# Main.net
KiCad netlist of a schematic drawn in Altium Designer
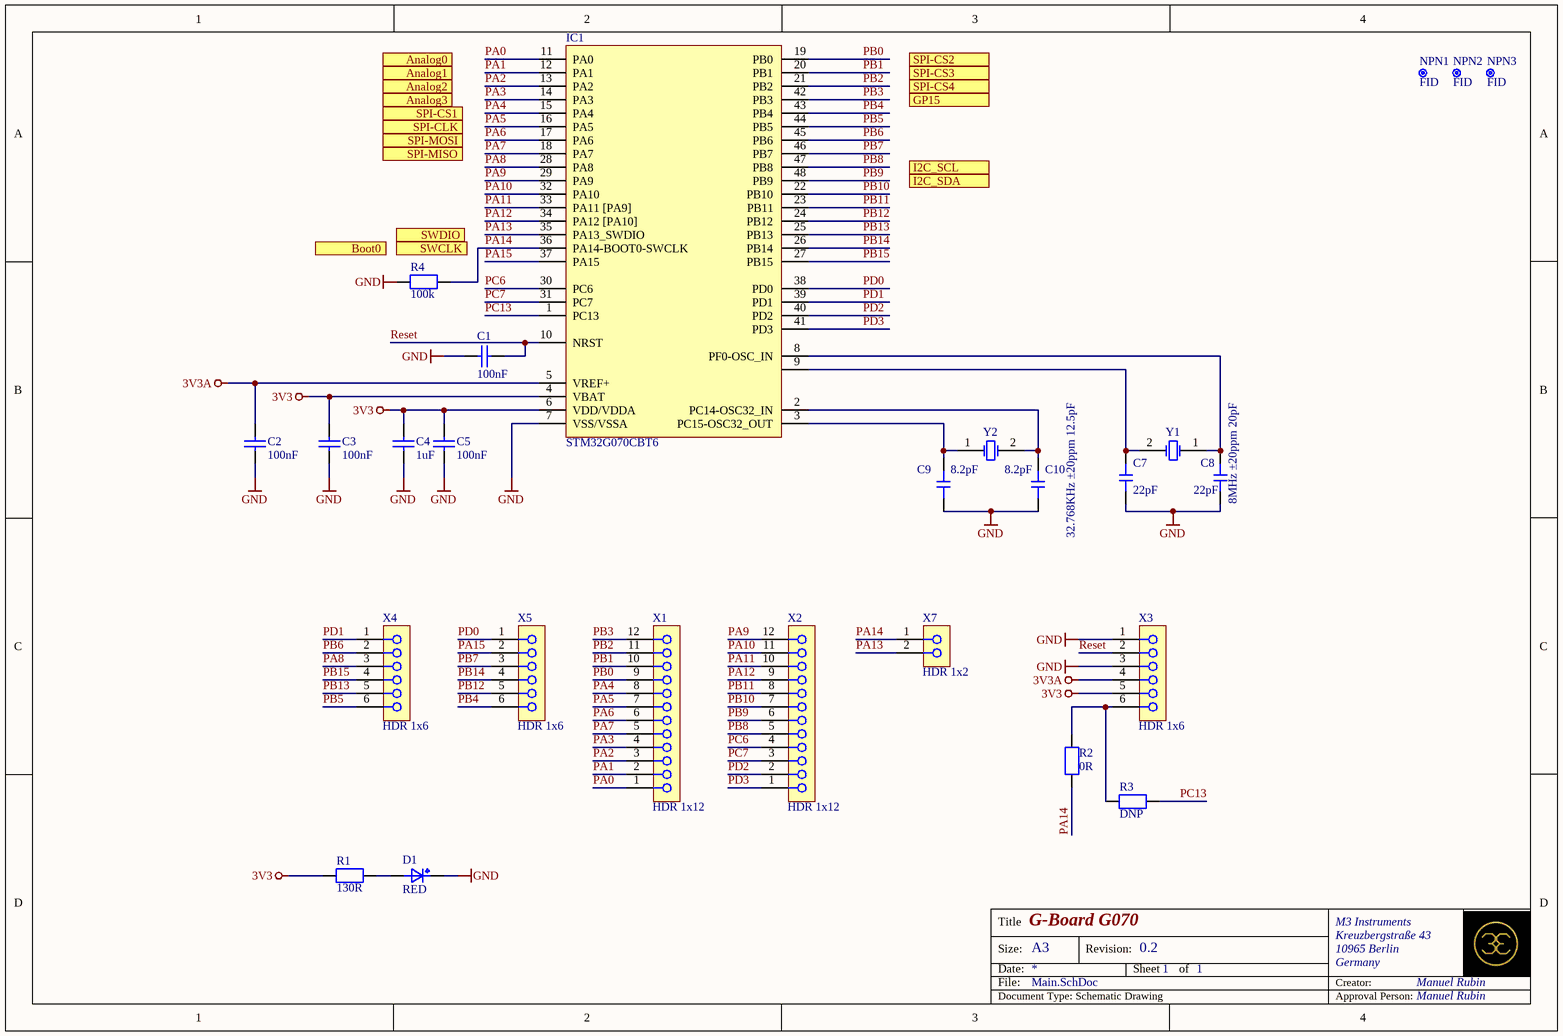
[diagram p0: Main.SchDoc]

(export (version "E")
  (design (tool "Eeschema 10.0.6"))
  (components
    (comp (ref "C1")
      (value "100nF")
      (footprint "CAPC1005X55")
      (description "X7R 100nF ±10% 16V 0402 Multilayer Ceramic Capacitors MLCC - SMD/SMT ROHS")
      (fields
        (field (name "MANUFACTURER") "Samsung Electro-Mechanics")
        (field (name "MANUFACTURER PART NUMBER") "CL05B104KO5NNNC")
      )
      (libsource (lib "Caps") (part "CAP_100nF_0402"))
    )
    (comp (ref "C2")
      (value "100nF")
      (footprint "CAPC1005X55")
      (description "X7R 100nF ±10% 16V 0402 Multilayer Ceramic Capacitors MLCC - SMD/SMT ROHS")
      (fields
        (field (name "MANUFACTURER") "Samsung Electro-Mechanics")
        (field (name "MANUFACTURER PART NUMBER") "CL05B104KO5NNNC")
      )
      (libsource (lib "Caps") (part "CAP_100nF_0402"))
    )
    (comp (ref "C3")
      (value "100nF")
      (footprint "CAPC1005X55")
      (description "X7R 100nF ±10% 16V 0402 Multilayer Ceramic Capacitors MLCC - SMD/SMT ROHS")
      (fields
        (field (name "MANUFACTURER") "Samsung Electro-Mechanics")
        (field (name "MANUFACTURER PART NUMBER") "CL05B104KO5NNNC")
      )
      (libsource (lib "Caps") (part "CAP_100nF_0402"))
    )
    (comp (ref "C4")
      (value "1uF")
      (footprint "CAPC1005X55")
      (description "X5R 25V ±10% 1uF 0402 Multilayer Ceramic Capacitors MLCC - SMD/SMT ROHS")
      (fields
        (field (name "MANUFACTURER") "Samsung Electro-Mechanics")
        (field (name "MANUFACTURER PART NUMBER") "CL05A105KA5NQNC")
      )
      (libsource (lib "Caps") (part "CAP_1uF_0402"))
    )
    (comp (ref "C5")
      (value "100nF")
      (footprint "CAPC1005X55")
      (description "X7R 100nF ±10% 16V 0402 Multilayer Ceramic Capacitors MLCC - SMD/SMT ROHS")
      (fields
        (field (name "MANUFACTURER") "Samsung Electro-Mechanics")
        (field (name "MANUFACTURER PART NUMBER") "CL05B104KO5NNNC")
      )
      (libsource (lib "Caps") (part "CAP_100nF_0402"))
    )
    (comp (ref "C7")
      (value "22pF")
      (footprint "CAPC1608X95N")
      (description "Chip capacitors")
      (fields
        (field (name "MANUFACTURER") "Samsung Electro-Mechanics")
        (field (name "MANUFACTURER PART NUMBER") "CL10C220JB8NNNC")
      )
      (libsource (lib "Caps") (part "CAP_22pF_50V_0603"))
    )
    (comp (ref "C8")
      (value "22pF")
      (footprint "CAPC1608X95N")
      (description "Chip capacitors")
      (fields
        (field (name "MANUFACTURER") "Samsung Electro-Mechanics")
        (field (name "MANUFACTURER PART NUMBER") "CL10C220JB8NNNC")
      )
      (libsource (lib "Caps") (part "CAP_22pF_50V_0603"))
    )
    (comp (ref "C9")
      (value "8.2pF")
      (footprint "CAPC1608X95N")
      (description "Multilayer Ceramic Capacitors MLCC - SMD/SMT 0402 8.0pF 50volts C0G +/-0.5pF")
      (fields
        (field (name "MANUFACTURER") "Guangdong Fenghua Advanced Tech")
        (field (name "MANUFACTURER PART NUMBER") "0603CG8R2C500NT")
      )
      (libsource (lib "Caps") (part "CAP_8p2_50V_0603"))
    )
    (comp (ref "C10")
      (value "8.2pF")
      (footprint "CAPC1608X95N")
      (description "Multilayer Ceramic Capacitors MLCC - SMD/SMT 0402 8.0pF 50volts C0G +/-0.5pF")
      (fields
        (field (name "MANUFACTURER") "Guangdong Fenghua Advanced Tech")
        (field (name "MANUFACTURER PART NUMBER") "0603CG8R2C500NT")
      )
      (libsource (lib "Caps") (part "CAP_8p2_50V_0603"))
    )
    (comp (ref "D1")
      (value "RED")
      (footprint "WL-SMCW_0805")
      (description "Standard LEDs - SMD WL-SMCW SMDMono TpVw Waterclr 0805 Red")
      (fields
        (field (name "MANUFACTURER") "Wurth Elektronik")
        (field (name "MANUFACTURER PART NUMBER") "150080RS75000")
      )
      (libsource (lib "Diodes") (part "LED_0805_RED_AK"))
    )
    (comp (ref "IC1")
      (value "STM32G070CBT6")
      (footprint "LQFP-48_7x7x05P")
      (fields (field (name "MANUFACTURER") "STMicroelectronics"))
      (libsource (lib "ICs") (part "STM32G070CBT6"))
    )
    (comp (ref "NPN1")
      (value "FID")
      (footprint "Fiducial_1mm")
      (libsource (lib "MISC") (part "Fiducial_1mm"))
    )
    (comp (ref "NPN2")
      (value "FID")
      (footprint "Fiducial_1mm")
      (libsource (lib "MISC") (part "Fiducial_1mm"))
    )
    (comp (ref "NPN3")
      (value "FID")
      (footprint "Fiducial_1mm")
      (libsource (lib "MISC") (part "Fiducial_1mm"))
    )
    (comp (ref "R1")
      (value "130R")
      (footprint "RESC2012X70N")
      (description "Dickfilmwiderstände - SMD 1/8watt 130ohms 1% 100ppm")
      (fields
        (field (name "MANUFACTURER") "Vishay / Dale")
        (field (name "MANUFACTURER PART NUMBER") "CRCW0805130RFKEA")
      )
      (libsource (lib "Resistors") (part "RES_130R_0805"))
    )
    (comp (ref "R2")
      (value "0R")
      (footprint "RESC1608X55N")
      (description "Thick Film Resistors - SMD 1/10watt ZEROohm Jumper")
      (fields
        (field (name "MANUFACTURER") "Vishay")
        (field (name "MANUFACTURER PART NUMBER") "CRCW06030000Z0EA")
      )
      (libsource (lib "Resistors") (part "RES_0R_0603"))
    )
    (comp (ref "R3")
      (value "DNP")
      (footprint "RESC1608X55N")
      (description "Resistor SMD 0603 - not populated")
      (libsource (lib "Resistors") (part "RES_DNF_0603"))
    )
    (comp (ref "R4")
      (value "100k")
      (footprint "RESC1005X40N")
      (description "Thick Film Resistors - SMD 63mW 100Kohms 1%")
      (fields
        (field (name "MANUFACTURER") "Vishay")
        (field (name "MANUFACTURER PART NUMBER") "RC0402FR-07100KL")
      )
      (libsource (lib "Gfs_Library") (part "RES_100k_0402"))
    )
    (comp (ref "X1")
      (value "HDR 1x12")
      (footprint "61301211121_no")
      (description "Board-to-Board-Steckverbinder, 2.54 mm, 12 Kontakt(e), Stiftleiste 1-Reihig")
      (fields (field (name "MANUFACTURER") "WE") (field (name "MANUFACTURER PART NUMBER") "61301211121"))
      (libsource (lib "Connectors") (part "CON_HEADER_1X12_no_overlay"))
    )
    (comp (ref "X2")
      (value "HDR 1x12")
      (footprint "61301211121_no")
      (description "Board-to-Board-Steckverbinder, 2.54 mm, 12 Kontakt(e), Stiftleiste 1-Reihig")
      (fields (field (name "MANUFACTURER") "WE") (field (name "MANUFACTURER PART NUMBER") "61301211121"))
      (libsource (lib "Connectors") (part "CON_HEADER_1X12_no_overlay"))
    )
    (comp (ref "X3")
      (value "HDR 1x6")
      (footprint "61300611121_no")
      (description "Board-to-Board-Steckverbinder, 2.54 mm, 6 Kontakt(e), Stiftleiste 1-Reihig")
      (fields (field (name "MANUFACTURER") "WE") (field (name "MANUFACTURER PART NUMBER") "61300611121"))
      (libsource (lib "Connectors") (part "CON_HEADER_1X6_no_overlay"))
    )
    (comp (ref "X4")
      (value "HDR 1x6")
      (footprint "61300611121_no")
      (description "Board-to-Board-Steckverbinder, 2.54 mm, 6 Kontakt(e), Stiftleiste 1-Reihig")
      (fields (field (name "MANUFACTURER") "WE") (field (name "MANUFACTURER PART NUMBER") "61300611121"))
      (libsource (lib "Connectors") (part "CON_HEADER_1X6_no_overlay"))
    )
    (comp (ref "X5")
      (value "HDR 1x6")
      (footprint "61300611121_no")
      (description "Board-to-Board-Steckverbinder, 2.54 mm, 6 Kontakt(e), Stiftleiste 1-Reihig")
      (fields (field (name "MANUFACTURER") "WE") (field (name "MANUFACTURER PART NUMBER") "61300611121"))
      (libsource (lib "Connectors") (part "CON_HEADER_1X6_no_overlay"))
    )
    (comp (ref "X7")
      (value "HDR 1x2")
      (footprint "CON_HEADER2.54_1x2W_no")
      (description "Board-to-Board-Steckverbinder, 2.54 mm, 2 Kontakt(e), Stiftleiste 1-Reihig")
      (fields
        (field (name "MANUFACTURER") "Samtec")
        (field (name "MANUFACTURER PART NUMBER") "TSW-102-07-T-S")
      )
      (libsource (lib "Connectors") (part "CON_HEADER_1X2_no_overlay"))
    )
    (comp (ref "Y1")
      (value "8MHz ±20ppm 20pF")
      (footprint "SMD-5032_2P")
      (description "8MHz SMD Crystal Resonator 20pF ±10ppm ±50ppm -40℃~+85℃ SMD5032-2P Crystals ROHS")
      (fields
        (field (name "MANUFACTURER") "Yangxing Tech")
        (field (name "MANUFACTURER PART NUMBER") "X50328MSB2GI")
      )
      (libsource (lib "MISC") (part "SMD-5032_2P 8MHz 20ppm 20pF"))
    )
    (comp (ref "Y2")
      (value "32.768KHz ±20ppm 12.5pF")
      (footprint "SMD-3215_2P FC - 135")
      (description "32.768kHz SMD Crystal Resonator 12.5pF 70kΩ ±20ppm -40℃~+85℃ SMD3215-2P Crystals ROHS")
      (fields
        (field (name "MANUFACTURER") "Seiko Epson")
        (field (name "MANUFACTURER PART NUMBER") "Q13FC1350000400")
      )
      (libsource (lib "MISC") (part "SMD-3215_2P 32.768KHz 20ppm 12.5pF"))
    )
  )
  (nets
    (net (code "9") (name "/PA0") (class "Default")
      (node (ref "IC1") (pin "11") (pinfunction "PA0_11") (pintype "passive"))
      (node (ref "X1") (pin "1") (pinfunction "1_1") (pintype "passive"))
    )
    (net (code "10") (name "/PA1") (class "Default")
      (node (ref "IC1") (pin "12") (pinfunction "PA1_12") (pintype "passive"))
      (node (ref "X1") (pin "2") (pinfunction "2_2") (pintype "passive"))
    )
    (net (code "11") (name "/PA2") (class "Default")
      (node (ref "IC1") (pin "13") (pinfunction "PA2_13") (pintype "passive"))
      (node (ref "X1") (pin "3") (pinfunction "3_3") (pintype "passive"))
    )
    (net (code "12") (name "/PA3") (class "Default")
      (node (ref "IC1") (pin "14") (pinfunction "PA3_14") (pintype "passive"))
      (node (ref "X1") (pin "4") (pinfunction "4_4") (pintype "passive"))
    )
    (net (code "13") (name "/PA4") (class "Default")
      (node (ref "IC1") (pin "15") (pinfunction "PA4_15") (pintype "passive"))
      (node (ref "X1") (pin "8") (pinfunction "8_8") (pintype "passive"))
    )
    (net (code "14") (name "/PA5") (class "Default")
      (node (ref "IC1") (pin "16") (pinfunction "PA5_16") (pintype "passive"))
      (node (ref "X1") (pin "7") (pinfunction "7_7") (pintype "passive"))
    )
    (net (code "15") (name "/PA6") (class "Default")
      (node (ref "IC1") (pin "17") (pinfunction "PA6_17") (pintype "passive"))
      (node (ref "X1") (pin "6") (pinfunction "6_6") (pintype "passive"))
    )
    (net (code "16") (name "/PA7") (class "Default")
      (node (ref "IC1") (pin "18") (pinfunction "PA7_18") (pintype "passive"))
      (node (ref "X1") (pin "5") (pinfunction "5_5") (pintype "passive"))
    )
    (net (code "17") (name "/PA8") (class "Default")
      (node (ref "IC1") (pin "28") (pinfunction "PA8_28") (pintype "passive"))
      (node (ref "X4") (pin "3") (pinfunction "3_3") (pintype "passive"))
    )
    (net (code "18") (name "/PA9") (class "Default")
      (node (ref "IC1") (pin "29") (pinfunction "PA9_29") (pintype "passive"))
      (node (ref "X2") (pin "12") (pinfunction "12_12") (pintype "passive"))
    )
    (net (code "19") (name "/PA10") (class "Default")
      (node (ref "IC1") (pin "32") (pinfunction "PA10_32") (pintype "passive"))
      (node (ref "X2") (pin "11") (pinfunction "11_11") (pintype "passive"))
    )
    (net (code "20") (name "/PA11") (class "Default")
      (node (ref "IC1") (pin "33") (pinfunction "PA11_[PA9]_33") (pintype "passive"))
      (node (ref "X2") (pin "10") (pinfunction "10_10") (pintype "passive"))
    )
    (net (code "21") (name "/PA12") (class "Default")
      (node (ref "IC1") (pin "34") (pinfunction "PA12_[PA10]_34") (pintype "passive"))
      (node (ref "X2") (pin "9") (pinfunction "9_9") (pintype "passive"))
    )
    (net (code "22") (name "/PA13") (class "Default")
      (node (ref "IC1") (pin "35") (pinfunction "PA13_SWDIO_35") (pintype "power_in"))
      (node (ref "X7") (pin "2") (pinfunction "2_2") (pintype "passive"))
    )
    (net (code "23") (name "/PA14") (class "Default")
      (node (ref "IC1") (pin "36") (pinfunction "PA14-BOOT0-SWCLK_36") (pintype "power_in"))
      (node (ref "R2") (pin "1") (pinfunction "1_1") (pintype "passive"))
      (node (ref "R4") (pin "1") (pinfunction "1_1") (pintype "passive"))
      (node (ref "X7") (pin "1") (pinfunction "1_1") (pintype "passive"))
    )
    (net (code "24") (name "/PA15") (class "Default")
      (node (ref "IC1") (pin "37") (pinfunction "PA15_37") (pintype "passive"))
      (node (ref "X5") (pin "2") (pinfunction "2_2") (pintype "passive"))
    )
    (net (code "25") (name "/PB0") (class "Default")
      (node (ref "IC1") (pin "19") (pinfunction "PB0_19") (pintype "passive"))
      (node (ref "X1") (pin "9") (pinfunction "9_9") (pintype "passive"))
    )
    (net (code "26") (name "/PB1") (class "Default")
      (node (ref "IC1") (pin "20") (pinfunction "PB1_20") (pintype "passive"))
      (node (ref "X1") (pin "10") (pinfunction "10_10") (pintype "passive"))
    )
    (net (code "27") (name "/PB2") (class "Default")
      (node (ref "IC1") (pin "21") (pinfunction "PB2_21") (pintype "passive"))
      (node (ref "X1") (pin "11") (pinfunction "11_11") (pintype "passive"))
    )
    (net (code "28") (name "/PB3") (class "Default")
      (node (ref "IC1") (pin "42") (pinfunction "PB3_42") (pintype "passive"))
      (node (ref "X1") (pin "12") (pinfunction "12_12") (pintype "passive"))
    )
    (net (code "29") (name "/PB4") (class "Default")
      (node (ref "IC1") (pin "43") (pinfunction "PB4_43") (pintype "passive"))
      (node (ref "X5") (pin "6") (pinfunction "6_6") (pintype "passive"))
    )
    (net (code "30") (name "/PB5") (class "Default")
      (node (ref "IC1") (pin "44") (pinfunction "PB5_44") (pintype "passive"))
      (node (ref "X4") (pin "6") (pinfunction "6_6") (pintype "passive"))
    )
    (net (code "31") (name "/PB6") (class "Default")
      (node (ref "IC1") (pin "45") (pinfunction "PB6_45") (pintype "passive"))
      (node (ref "X4") (pin "2") (pinfunction "2_2") (pintype "passive"))
    )
    (net (code "32") (name "/PB7") (class "Default")
      (node (ref "IC1") (pin "46") (pinfunction "PB7_46") (pintype "passive"))
      (node (ref "X5") (pin "3") (pinfunction "3_3") (pintype "passive"))
    )
    (net (code "33") (name "/PB8") (class "Default")
      (node (ref "IC1") (pin "47") (pinfunction "PB8_47") (pintype "power_in"))
      (node (ref "X2") (pin "5") (pinfunction "5_5") (pintype "passive"))
    )
    (net (code "34") (name "/PB9") (class "Default")
      (node (ref "IC1") (pin "48") (pinfunction "PB9_48") (pintype "power_in"))
      (node (ref "X2") (pin "6") (pinfunction "6_6") (pintype "passive"))
    )
    (net (code "35") (name "/PB10") (class "Default")
      (node (ref "IC1") (pin "22") (pinfunction "PB10_22") (pintype "passive"))
      (node (ref "X2") (pin "7") (pinfunction "7_7") (pintype "passive"))
    )
    (net (code "36") (name "/PB11") (class "Default")
      (node (ref "IC1") (pin "23") (pinfunction "PB11_23") (pintype "power_in"))
      (node (ref "X2") (pin "8") (pinfunction "8_8") (pintype "passive"))
    )
    (net (code "37") (name "/PB12") (class "Default")
      (node (ref "IC1") (pin "24") (pinfunction "PB12_24") (pintype "power_in"))
      (node (ref "X5") (pin "5") (pinfunction "5_5") (pintype "passive"))
    )
    (net (code "38") (name "/PB13") (class "Default")
      (node (ref "IC1") (pin "25") (pinfunction "PB13_25") (pintype "passive"))
      (node (ref "X4") (pin "5") (pinfunction "5_5") (pintype "passive"))
    )
    (net (code "39") (name "/PB14") (class "Default")
      (node (ref "IC1") (pin "26") (pinfunction "PB14_26") (pintype "passive"))
      (node (ref "X5") (pin "4") (pinfunction "4_4") (pintype "passive"))
    )
    (net (code "40") (name "/PB15") (class "Default")
      (node (ref "IC1") (pin "27") (pinfunction "PB15_27") (pintype "passive"))
      (node (ref "X4") (pin "4") (pinfunction "4_4") (pintype "passive"))
    )
    (net (code "41") (name "/PC6") (class "Default")
      (node (ref "IC1") (pin "30") (pinfunction "PC6_30") (pintype "passive"))
      (node (ref "X2") (pin "4") (pinfunction "4_4") (pintype "passive"))
    )
    (net (code "42") (name "/PC7") (class "Default")
      (node (ref "IC1") (pin "31") (pinfunction "PC7_31") (pintype "passive"))
      (node (ref "X2") (pin "3") (pinfunction "3_3") (pintype "passive"))
    )
    (net (code "43") (name "/PC13") (class "Default")
      (node (ref "IC1") (pin "1") (pinfunction "PC13_1") (pintype "power_in"))
      (node (ref "R3") (pin "2") (pinfunction "2_2") (pintype "passive"))
    )
    (net (code "44") (name "/PD0") (class "Default")
      (node (ref "IC1") (pin "38") (pinfunction "PD0_38") (pintype "passive"))
      (node (ref "X5") (pin "1") (pinfunction "1_1") (pintype "passive"))
    )
    (net (code "45") (name "/PD1") (class "Default")
      (node (ref "IC1") (pin "39") (pinfunction "PD1_39") (pintype "passive"))
      (node (ref "X4") (pin "1") (pinfunction "1_1") (pintype "passive"))
    )
    (net (code "46") (name "/PD2") (class "Default")
      (node (ref "IC1") (pin "40") (pinfunction "PD2_40") (pintype "passive"))
      (node (ref "X2") (pin "2") (pinfunction "2_2") (pintype "passive"))
    )
    (net (code "47") (name "/PD3") (class "Default")
      (node (ref "IC1") (pin "41") (pinfunction "PD3_41") (pintype "passive"))
      (node (ref "X2") (pin "1") (pinfunction "1_1") (pintype "passive"))
    )
    (net (code "48") (name "/Reset") (class "Default")
      (node (ref "C1") (pin "1") (pinfunction "1_1") (pintype "passive"))
      (node (ref "IC1") (pin "10") (pinfunction "NRST_10") (pintype "passive"))
      (node (ref "X3") (pin "2") (pinfunction "2_2") (pintype "passive"))
    )
    (net (code "58") (name "3V3") (class "Default")
      (node (ref "C3") (pin "2") (pinfunction "2_2") (pintype "passive"))
      (node (ref "C4") (pin "2") (pinfunction "2_2") (pintype "passive"))
      (node (ref "C5") (pin "2") (pinfunction "2_2") (pintype "passive"))
      (node (ref "IC1") (pin "4") (pinfunction "VBAT_4") (pintype "passive"))
      (node (ref "IC1") (pin "6") (pinfunction "VDD/VDDA_6") (pintype "passive"))
      (node (ref "R1") (pin "1") (pinfunction "1_1") (pintype "passive"))
      (node (ref "X3") (pin "5") (pinfunction "5_5") (pintype "passive"))
    )
    (net (code "59") (name "3V3A") (class "Default")
      (node (ref "C2") (pin "2") (pinfunction "2_2") (pintype "passive"))
      (node (ref "IC1") (pin "5") (pinfunction "VREF+_5") (pintype "passive"))
      (node (ref "X3") (pin "4") (pinfunction "4_4") (pintype "passive"))
    )
    (net (code "60") (name "GND") (class "Default")
      (node (ref "C1") (pin "2") (pinfunction "2_2") (pintype "passive"))
      (node (ref "C10") (pin "1") (pinfunction "1_1") (pintype "passive"))
      (node (ref "C2") (pin "1") (pinfunction "1_1") (pintype "passive"))
      (node (ref "C3") (pin "1") (pinfunction "1_1") (pintype "passive"))
      (node (ref "C4") (pin "1") (pinfunction "1_1") (pintype "passive"))
      (node (ref "C5") (pin "1") (pinfunction "1_1") (pintype "passive"))
      (node (ref "C7") (pin "2") (pinfunction "2_2") (pintype "passive"))
      (node (ref "C8") (pin "2") (pinfunction "2_2") (pintype "passive"))
      (node (ref "C9") (pin "1") (pinfunction "1_1") (pintype "passive"))
      (node (ref "D1") (pin "K") (pinfunction "K_K") (pintype "passive"))
      (node (ref "IC1") (pin "7") (pinfunction "VSS/VSSA_7") (pintype "passive"))
      (node (ref "R4") (pin "2") (pinfunction "2_2") (pintype "passive"))
      (node (ref "X3") (pin "1") (pinfunction "1_1") (pintype "passive"))
      (node (ref "X3") (pin "3") (pinfunction "3_3") (pintype "passive"))
    )
    (net (code "61") (name "Net-(D1-PadA)") (class "Default")
      (node (ref "D1") (pin "A") (pinfunction "A_A") (pintype "passive"))
      (node (ref "R1") (pin "2") (pinfunction "2_2") (pintype "passive"))
    )
    (net (code "62") (name "Net-(IC1-PC14-OSC32_IN)") (class "Default")
      (node (ref "C10") (pin "2") (pinfunction "2_2") (pintype "passive"))
      (node (ref "IC1") (pin "2") (pinfunction "PC14-OSC32_IN_2") (pintype "passive"))
      (node (ref "Y2") (pin "2") (pinfunction "OSC2_2") (pintype "passive"))
    )
    (net (code "63") (name "Net-(IC1-PC15-OSC32_OUT)") (class "Default")
      (node (ref "C9") (pin "2") (pinfunction "2_2") (pintype "passive"))
      (node (ref "IC1") (pin "3") (pinfunction "PC15-OSC32_OUT_3") (pintype "passive"))
      (node (ref "Y2") (pin "1") (pinfunction "OSC1_1") (pintype "passive"))
    )
    (net (code "64") (name "Net-(IC1-PF0-OSC_IN)") (class "Default")
      (node (ref "C8") (pin "1") (pinfunction "1_1") (pintype "passive"))
      (node (ref "IC1") (pin "8") (pinfunction "PF0-OSC_IN_8") (pintype "power_in"))
      (node (ref "Y1") (pin "1") (pinfunction "OSC1_1") (pintype "passive"))
    )
    (net (code "65") (name "Net-(IC1-PF1-OSC_OU'T)") (class "Default")
      (node (ref "C7") (pin "1") (pinfunction "1_1") (pintype "passive"))
      (node (ref "IC1") (pin "9") (pinfunction "PF1-OSC_OU'T_9") (pintype "power_in"))
      (node (ref "Y1") (pin "2") (pinfunction "OSC2_2") (pintype "passive"))
    )
    (net (code "66") (name "Net-(R2-Pad2)") (class "Default")
      (node (ref "R2") (pin "2") (pinfunction "2_2") (pintype "passive"))
      (node (ref "R3") (pin "1") (pinfunction "1_1") (pintype "passive"))
      (node (ref "X3") (pin "6") (pinfunction "6_6") (pintype "passive"))
    )
  )
)
